# PMSM_500W_Controller_MCU.net
KiCad netlist of a schematic drawn in Altium Designer
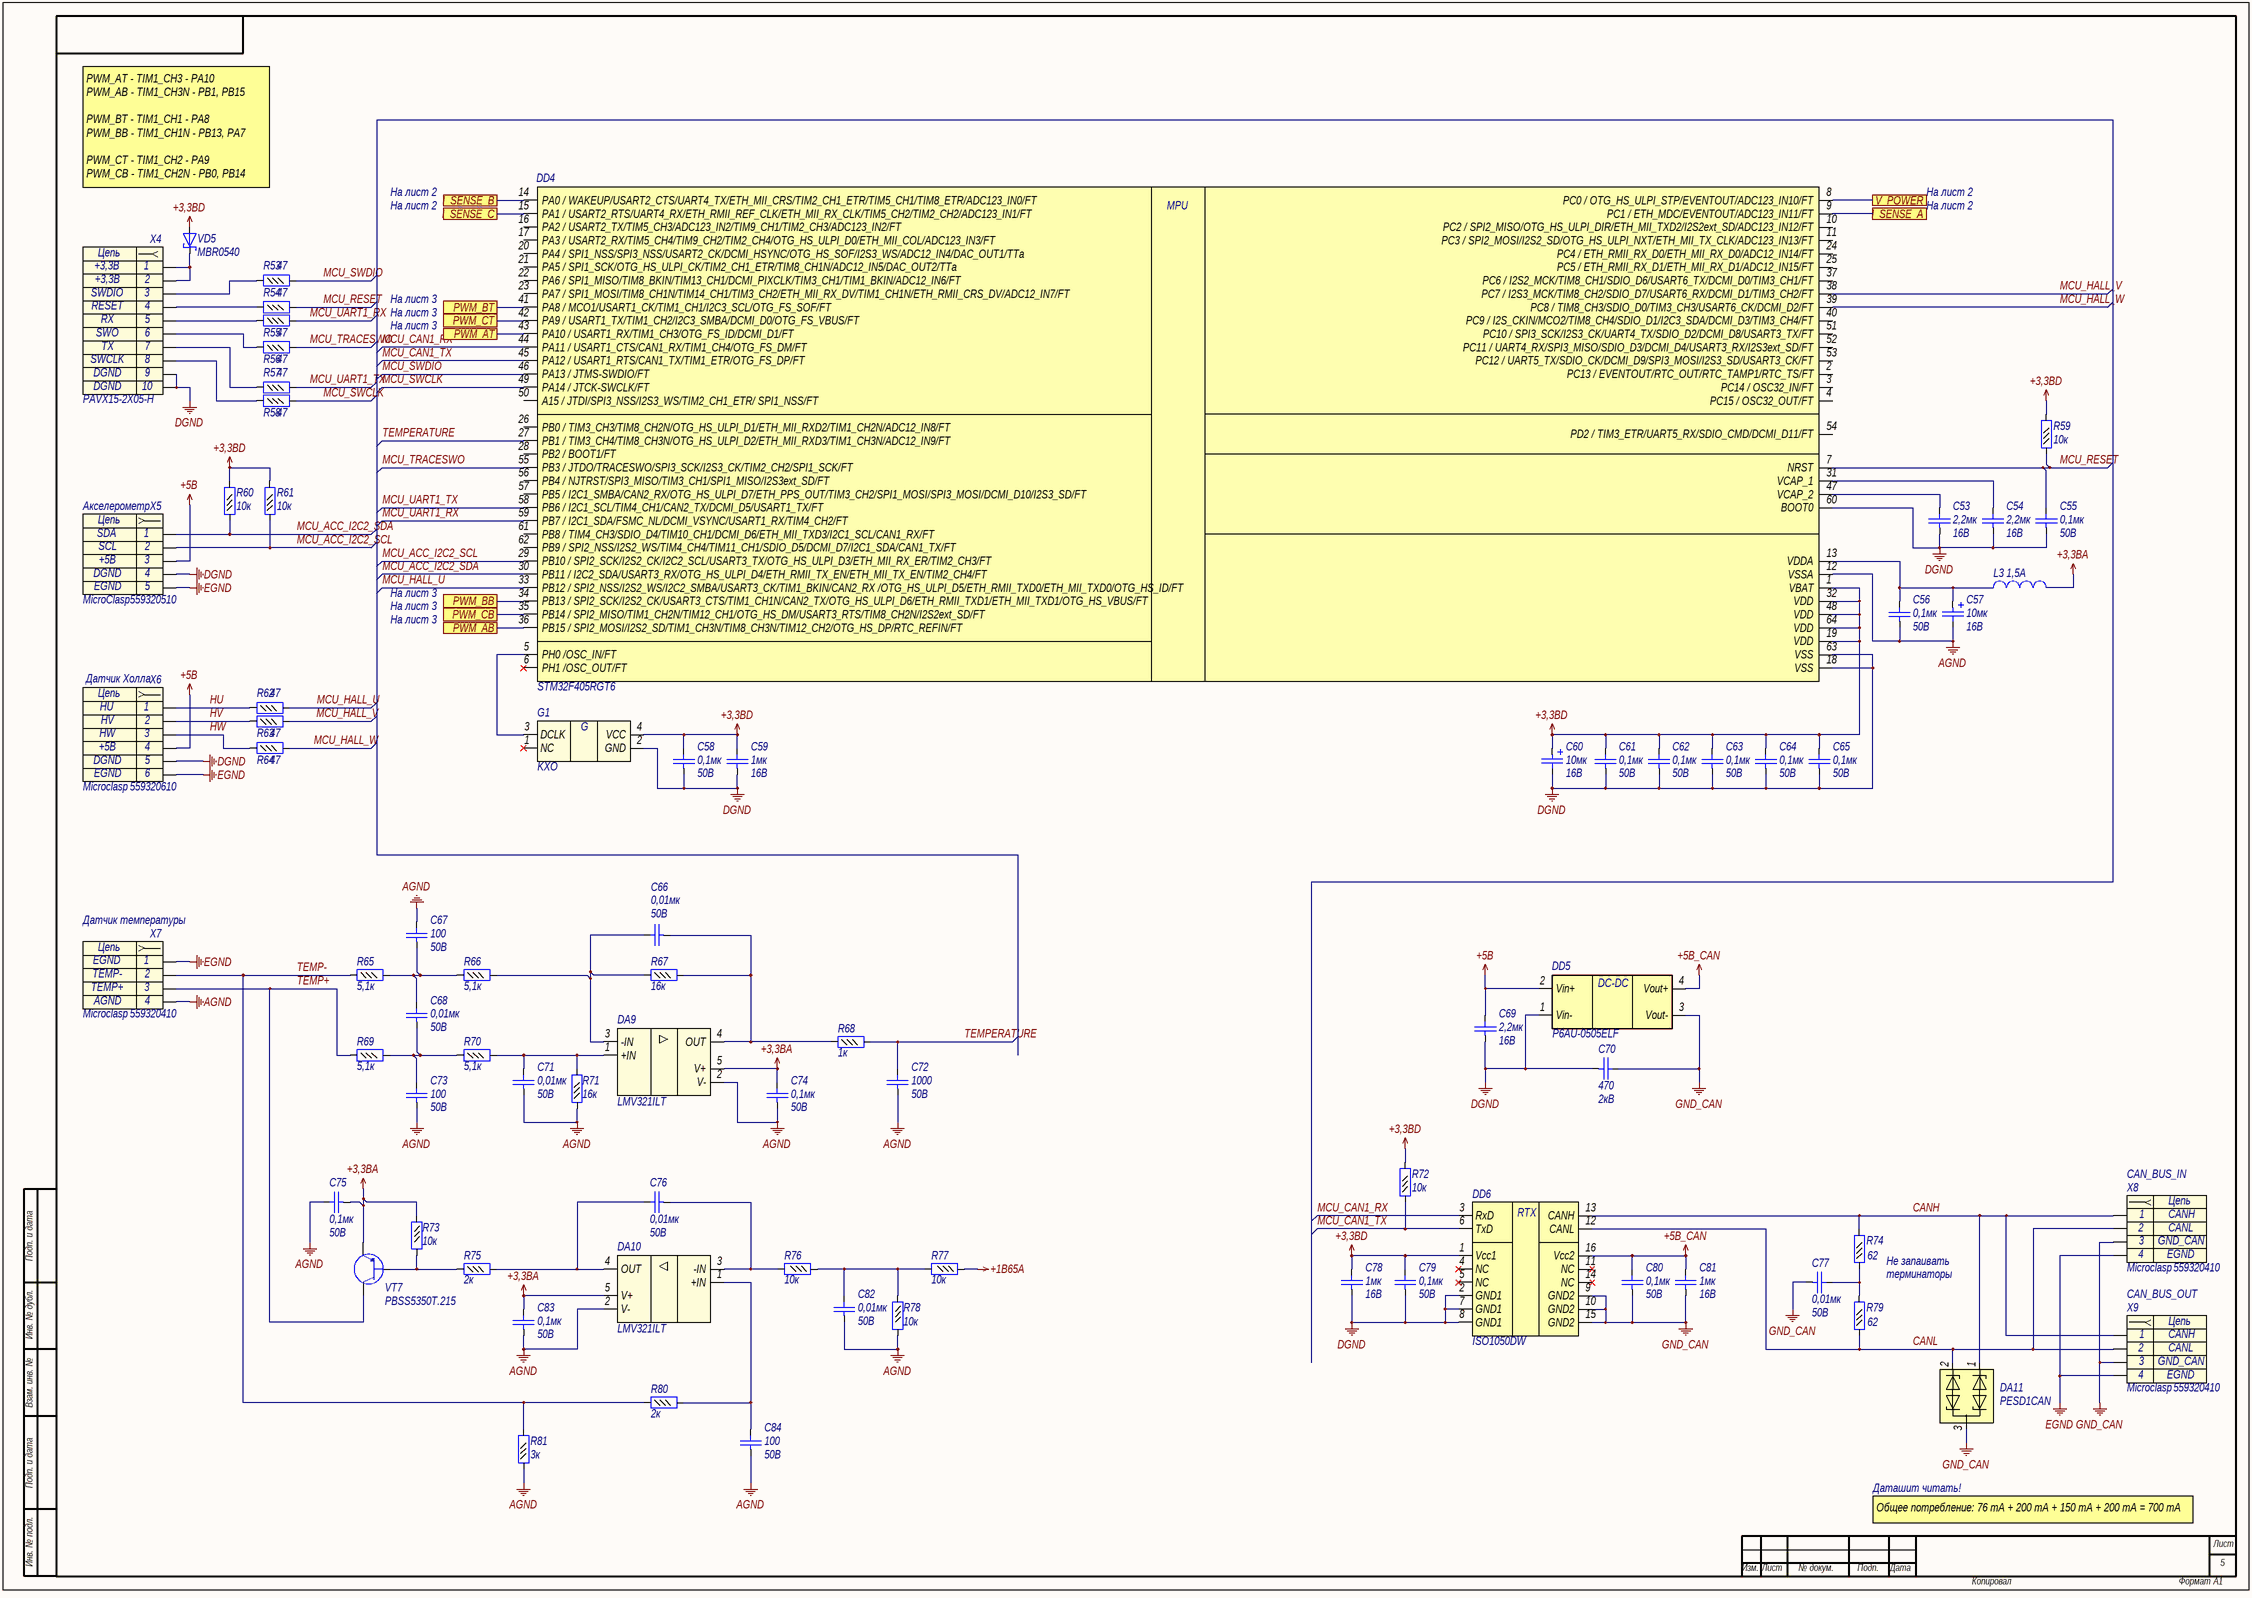
[diagram p0: PMSM_500W_Controller_MCU.SchDoc]

(export (version "E")
  (design (tool "Eeschema 10.0.6"))
  (components
    (comp (ref "C53")
      (value "2,2мк")
      (footprint "C0603")
      (description "Конденсатор")
      (fields (field (name "VOLTAGE") "16B") (field (name "PART NUMBER") "GRM188Z71C225ME43J"))
      (libsource (lib "MOP44") (part "Capacitor"))
    )
    (comp (ref "C54")
      (value "2,2мк")
      (footprint "C0603")
      (description "Конденсатор")
      (fields (field (name "VOLTAGE") "16B") (field (name "PART NUMBER") "GRM188Z71C225ME43J"))
      (libsource (lib "MOP44") (part "Capacitor"))
    )
    (comp (ref "C55")
      (value "0,1мк")
      (footprint "C0402")
      (description "Конденсатор")
      (fields
        (field (name "VOLTAGE") "50В")
        (field (name "PART NUMBER") "GRM155R71H104KE14D")
        (field (name "Comment") "Capacitor")
      )
      (libsource (lib "MOP44") (part "Capacitor"))
    )
    (comp (ref "C56")
      (value "0,1мк")
      (footprint "C0402")
      (description "Конденсатор")
      (fields
        (field (name "VOLTAGE") "50В")
        (field (name "PART NUMBER") "GRM155R71H104KE14D")
        (field (name "Comment") "Capacitor")
      )
      (libsource (lib "MOP44") (part "Capacitor"))
    )
    (comp (ref "C57")
      (value "10мк")
      (footprint "TANTAL CASE A")
      (description "Конденсатор полярный")
      (fields
        (field (name "VOLTAGE") "16В")
        (field (name "PART NUMBER") "293D106X9016A2TE3")
        (field (name "Comment") "Capacitor_pol")
      )
      (libsource (lib "MOP44") (part "Capacitor_pol"))
    )
    (comp (ref "C58")
      (value "0,1мк")
      (footprint "C0402")
      (description "Конденсатор")
      (fields
        (field (name "VOLTAGE") "50В")
        (field (name "PART NUMBER") "GRM155R71H104KE14D")
        (field (name "Comment") "Capacitor")
      )
      (libsource (lib "MOP44") (part "Capacitor"))
    )
    (comp (ref "C59")
      (value "1мк")
      (footprint "C0603")
      (description "Конденсатор")
      (fields
        (field (name "VOLTAGE") "16B")
        (field (name "PART NUMBER") "GRM188R71C105KA12D**")
        (field (name "Comment") "Capacitor")
      )
      (libsource (lib "MOP44") (part "Capacitor"))
    )
    (comp (ref "C60")
      (value "10мк")
      (footprint "TANTAL CASE A")
      (description "Конденсатор полярный")
      (fields
        (field (name "VOLTAGE") "16В")
        (field (name "PART NUMBER") "293D106X9016A2TE3")
        (field (name "Comment") "Capacitor_pol")
      )
      (libsource (lib "MOP44") (part "Capacitor_pol"))
    )
    (comp (ref "C61")
      (value "0,1мк")
      (footprint "C0402")
      (description "Конденсатор")
      (fields
        (field (name "VOLTAGE") "50В")
        (field (name "PART NUMBER") "GRM155R71H104KE14D")
        (field (name "Comment") "Capacitor")
      )
      (libsource (lib "MOP44") (part "Capacitor"))
    )
    (comp (ref "C62")
      (value "0,1мк")
      (footprint "C0402")
      (description "Конденсатор")
      (fields
        (field (name "VOLTAGE") "50В")
        (field (name "PART NUMBER") "GRM155R71H104KE14D")
        (field (name "Comment") "Capacitor")
      )
      (libsource (lib "MOP44") (part "Capacitor"))
    )
    (comp (ref "C63")
      (value "0,1мк")
      (footprint "C0402")
      (description "Конденсатор")
      (fields
        (field (name "VOLTAGE") "50В")
        (field (name "PART NUMBER") "GRM155R71H104KE14D")
        (field (name "Comment") "Capacitor")
      )
      (libsource (lib "MOP44") (part "Capacitor"))
    )
    (comp (ref "C64")
      (value "0,1мк")
      (footprint "C0402")
      (description "Конденсатор")
      (fields
        (field (name "VOLTAGE") "50В")
        (field (name "PART NUMBER") "GRM155R71H104KE14D")
        (field (name "Comment") "Capacitor")
      )
      (libsource (lib "MOP44") (part "Capacitor"))
    )
    (comp (ref "C65")
      (value "0,1мк")
      (footprint "C0402")
      (description "Конденсатор")
      (fields
        (field (name "VOLTAGE") "50В")
        (field (name "PART NUMBER") "GRM155R71H104KE14D")
        (field (name "Comment") "Capacitor")
      )
      (libsource (lib "MOP44") (part "Capacitor"))
    )
    (comp (ref "C66")
      (value "0,01мк")
      (footprint "C0402")
      (description "Конденсатор")
      (fields
        (field (name "VOLTAGE") "50B")
        (field (name "PART NUMBER") "GRM155R71H103K")
        (field (name "Comment") "Capacitor")
      )
      (libsource (lib "MOP44") (part "Capacitor"))
    )
    (comp (ref "C67")
      (value "100")
      (footprint "C0402")
      (description "Конденсатор")
      (fields
        (field (name "VOLTAGE") "50B")
        (field (name "PART NUMBER") "GRM1535C1H101J")
        (field (name "Comment") "Capacitor")
      )
      (libsource (lib "MOP44") (part "Capacitor"))
    )
    (comp (ref "C68")
      (value "0,01мк")
      (footprint "C0402")
      (description "Конденсатор")
      (fields
        (field (name "VOLTAGE") "50B")
        (field (name "PART NUMBER") "GRM155R71H103K")
        (field (name "Comment") "Capacitor")
      )
      (libsource (lib "MOP44") (part "Capacitor"))
    )
    (comp (ref "C69")
      (value "2,2мк")
      (footprint "C0603")
      (description "Конденсатор")
      (fields (field (name "VOLTAGE") "16B") (field (name "PART NUMBER") "GRM188Z71C225ME43J"))
      (libsource (lib "MOP44") (part "Capacitor"))
    )
    (comp (ref "C70")
      (value "470")
      (footprint "C1206")
      (description "Конденсатор")
      (fields
        (field (name "VOLTAGE") "2кВ")
        (field (name "PART NUMBER") "CC1206KKX7RDBB471")
        (field (name "Comment") "Capacitor")
      )
      (libsource (lib "MOP44") (part "Capacitor"))
    )
    (comp (ref "C71")
      (value "0,01мк")
      (footprint "C0402")
      (description "Конденсатор")
      (fields
        (field (name "VOLTAGE") "50B")
        (field (name "PART NUMBER") "GRM155R71H103K")
        (field (name "Comment") "Capacitor")
      )
      (libsource (lib "MOP44") (part "Capacitor"))
    )
    (comp (ref "C72")
      (value "1000")
      (footprint "C0402")
      (description "Конденсатор")
      (fields
        (field (name "VOLTAGE") "50B")
        (field (name "PART NUMBER") "GRM1555C1H102J")
        (field (name "Comment") "Capacitor")
      )
      (libsource (lib "MOP44") (part "Capacitor"))
    )
    (comp (ref "C73")
      (value "100")
      (footprint "C0402")
      (description "Конденсатор")
      (fields
        (field (name "VOLTAGE") "50B")
        (field (name "PART NUMBER") "GRM1535C1H101J")
        (field (name "Comment") "Capacitor")
      )
      (libsource (lib "MOP44") (part "Capacitor"))
    )
    (comp (ref "C74")
      (value "0,1мк")
      (footprint "C0402")
      (description "Конденсатор")
      (fields
        (field (name "VOLTAGE") "50В")
        (field (name "PART NUMBER") "GRM155R71H104KE14D")
        (field (name "Comment") "Capacitor")
      )
      (libsource (lib "MOP44") (part "Capacitor"))
    )
    (comp (ref "C75")
      (value "0,1мк")
      (footprint "C0402")
      (description "Конденсатор")
      (fields
        (field (name "VOLTAGE") "50В")
        (field (name "PART NUMBER") "GRM155R71H104KE14D")
        (field (name "Comment") "Capacitor")
      )
      (libsource (lib "MOP44") (part "Capacitor"))
    )
    (comp (ref "C76")
      (value "0,01мк")
      (footprint "C0402")
      (description "Конденсатор")
      (fields
        (field (name "VOLTAGE") "50B")
        (field (name "PART NUMBER") "GRM155R71H103K")
        (field (name "Comment") "Capacitor")
      )
      (libsource (lib "MOP44") (part "Capacitor"))
    )
    (comp (ref "C77")
      (value "0,01мк")
      (footprint "C0402")
      (description "Конденсатор")
      (fields
        (field (name "VOLTAGE") "50B")
        (field (name "PART NUMBER") "GRM155R71H103K")
        (field (name "Comment") "Capacitor")
      )
      (libsource (lib "MOP44") (part "Capacitor"))
    )
    (comp (ref "C78")
      (value "1мк")
      (footprint "C0603")
      (description "Конденсатор")
      (fields
        (field (name "VOLTAGE") "16B")
        (field (name "PART NUMBER") "GRM188R71C105KA12D**")
        (field (name "Comment") "Capacitor")
      )
      (libsource (lib "MOP44") (part "Capacitor"))
    )
    (comp (ref "C79")
      (value "0,1мк")
      (footprint "C0402")
      (description "Конденсатор")
      (fields
        (field (name "VOLTAGE") "50В")
        (field (name "PART NUMBER") "GRM155R71H104KE14D")
        (field (name "Comment") "Capacitor")
      )
      (libsource (lib "MOP44") (part "Capacitor"))
    )
    (comp (ref "C80")
      (value "0,1мк")
      (footprint "C0402")
      (description "Конденсатор")
      (fields
        (field (name "VOLTAGE") "50В")
        (field (name "PART NUMBER") "GRM155R71H104KE14D")
        (field (name "Comment") "Capacitor")
      )
      (libsource (lib "MOP44") (part "Capacitor"))
    )
    (comp (ref "C81")
      (value "1мк")
      (footprint "C0603")
      (description "Конденсатор")
      (fields
        (field (name "VOLTAGE") "16B")
        (field (name "PART NUMBER") "GRM188R71C105KA12D**")
        (field (name "Comment") "Capacitor")
      )
      (libsource (lib "MOP44") (part "Capacitor"))
    )
    (comp (ref "C82")
      (value "0,01мк")
      (footprint "C0402")
      (description "Конденсатор")
      (fields
        (field (name "VOLTAGE") "50B")
        (field (name "PART NUMBER") "GRM155R71H103K")
        (field (name "Comment") "Capacitor")
      )
      (libsource (lib "MOP44") (part "Capacitor"))
    )
    (comp (ref "C83")
      (value "0,1мк")
      (footprint "C0402")
      (description "Конденсатор")
      (fields
        (field (name "VOLTAGE") "50В")
        (field (name "PART NUMBER") "GRM155R71H104KE14D")
        (field (name "Comment") "Capacitor")
      )
      (libsource (lib "MOP44") (part "Capacitor"))
    )
    (comp (ref "C84")
      (value "100")
      (footprint "C0402")
      (description "Конденсатор")
      (fields
        (field (name "VOLTAGE") "50B")
        (field (name "PART NUMBER") "GRM1535C1H101J")
        (field (name "Comment") "Capacitor")
      )
      (libsource (lib "MOP44") (part "Capacitor"))
    )
    (comp (ref "DA9")
      (value "LMV321ILT")
      (footprint "SOT23-5")
      (description "HIGH-DRIVE OPERATIONAL AMPLIFIERS WITH SHUTDOWN")
      (libsource (lib "") (part "LMV321ILT_1"))
    )
    (comp (ref "DA10")
      (value "LMV321ILT")
      (footprint "SOT23-5")
      (description "HIGH-DRIVE OPERATIONAL AMPLIFIERS WITH SHUTDOWN")
      (libsource (lib "MOP44") (part "LMV321ILT"))
    )
    (comp (ref "DA11")
      (value "PESD")
      (footprint "SOT23-3")
      (description "TVS")
      (fields (field (name "PART NUMBER") "PESD1CAN"))
      (libsource (lib "MOP44") (part "PESD"))
    )
    (comp (ref "DD4")
      (value "STM32F405RGT6")
      (footprint "LQFP64")
      (libsource (lib "MOP44") (part "STM32F405RGT6"))
    )
    (comp (ref "DD5")
      (value "P6AU-xxxxELF")
      (footprint "SIP4")
      (description "DC/DC преобразователь")
      (fields (field (name "PART NUMBER") "P6AU-0505ELF") (field (name "MANUFACTURER") "PEAK Electronics"))
      (libsource (lib "MOP44") (part "P6AU-xxxxELF"))
    )
    (comp (ref "DD6")
      (value "~")
      (footprint "SO16")
      (description "Isolated CAN Transceiver")
      (fields (field (name "PART NUMBER") "ISO1050DW"))
      (libsource (lib "MOP44") (part "ISO1050DW"))
    )
    (comp (ref "G1")
      (value "KXO")
      (footprint "QSMD7x5.2x1.8")
      (description "Кварц. генер. 32.768 МГц (HCMOS/TTL)")
      (fields (field (name "PART NUMBER") "KXO-V97"))
      (libsource (lib "MOP44") (part "KXO"))
    )
    (comp (ref "L3")
      (value "Inductor")
      (footprint "L0603")
      (description "EMI Suppression Filter")
      (fields (field (name "RATED CURRENT") "1,5A") (field (name "PART NUMBER") "BLM18PG181SN1D"))
      (libsource (lib "MOP44") (part "Inductor"))
    )
    (comp (ref "R53")
      (value "47")
      (footprint "R0402")
      (description "Резистор")
      (fields (field (name "PART NUMBER") "RC0402FR-0747RL") (field (name "POWER") "0,062Вт"))
      (libsource (lib "MOP44") (part "Resistor_0,062Вт"))
    )
    (comp (ref "R54")
      (value "47")
      (footprint "R0402")
      (description "Резистор")
      (fields (field (name "PART NUMBER") "RC0402FR-0747RL") (field (name "POWER") "0,062Вт"))
      (libsource (lib "MOP44") (part "Resistor_0,062Вт"))
    )
    (comp (ref "R55")
      (value "47")
      (footprint "R0402")
      (description "Резистор")
      (fields (field (name "PART NUMBER") "RC0402FR-0747RL") (field (name "POWER") "0,062Вт"))
      (libsource (lib "MOP44") (part "Resistor_0,062Вт"))
    )
    (comp (ref "R56")
      (value "47")
      (footprint "R0402")
      (description "Резистор")
      (fields (field (name "PART NUMBER") "RC0402FR-0747RL") (field (name "POWER") "0,062Вт"))
      (libsource (lib "MOP44") (part "Resistor_0,062Вт"))
    )
    (comp (ref "R57")
      (value "47")
      (footprint "R0402")
      (description "Резистор")
      (fields (field (name "PART NUMBER") "RC0402FR-0747RL") (field (name "POWER") "0,062Вт"))
      (libsource (lib "MOP44") (part "Resistor_0,062Вт"))
    )
    (comp (ref "R58")
      (value "47")
      (footprint "R0402")
      (description "Резистор")
      (fields (field (name "PART NUMBER") "RC0402FR-0747RL") (field (name "POWER") "0,062Вт"))
      (libsource (lib "MOP44") (part "Resistor_0,062Вт"))
    )
    (comp (ref "R59")
      (value "10к")
      (footprint "R0402")
      (description "Резистор")
      (fields (field (name "PART NUMBER") "RC0402FR-0710KL") (field (name "POWER") "0,062Вт"))
      (libsource (lib "") (part "Resistor_0,062Вт_2"))
    )
    (comp (ref "R60")
      (value "10к")
      (footprint "R0402")
      (description "Резистор")
      (fields (field (name "PART NUMBER") "RC0402FR-0710KL") (field (name "POWER") "0,062Вт"))
      (libsource (lib "") (part "Resistor_0,062Вт_2"))
    )
    (comp (ref "R61")
      (value "10к")
      (footprint "R0402")
      (description "Резистор")
      (fields (field (name "PART NUMBER") "RC0402FR-0710KL") (field (name "POWER") "0,062Вт"))
      (libsource (lib "") (part "Resistor_0,062Вт_2"))
    )
    (comp (ref "R62")
      (value "47")
      (footprint "R0402")
      (description "Резистор")
      (fields (field (name "PART NUMBER") "RC0402FR-0747RL") (field (name "POWER") "0,062Вт"))
      (libsource (lib "MOP44") (part "Resistor_0,062Вт"))
    )
    (comp (ref "R63")
      (value "47")
      (footprint "R0402")
      (description "Резистор")
      (fields (field (name "PART NUMBER") "RC0402FR-0747RL") (field (name "POWER") "0,062Вт"))
      (libsource (lib "MOP44") (part "Resistor_0,062Вт"))
    )
    (comp (ref "R64")
      (value "47")
      (footprint "R0402")
      (description "Резистор")
      (fields (field (name "PART NUMBER") "RC0402FR-0747RL") (field (name "POWER") "0,062Вт"))
      (libsource (lib "MOP44") (part "Resistor_0,062Вт"))
    )
    (comp (ref "R65")
      (value "5,1к")
      (footprint "R0402")
      (description "Резистор")
      (fields (field (name "PART NUMBER") "RC0402FR-075K1") (field (name "POWER") "0,062Вт"))
      (libsource (lib "MOP44") (part "Resistor_0,062Вт"))
    )
    (comp (ref "R66")
      (value "5,1к")
      (footprint "R0402")
      (description "Резистор")
      (fields (field (name "PART NUMBER") "RC0402FR-075K1") (field (name "POWER") "0,062Вт"))
      (libsource (lib "MOP44") (part "Resistor_0,062Вт"))
    )
    (comp (ref "R67")
      (value "16к")
      (footprint "R0402")
      (description "Резистор")
      (fields (field (name "PART NUMBER") "RC0402FR-0716KL") (field (name "POWER") "0,062Вт"))
      (libsource (lib "MOP44") (part "Resistor_0,062Вт"))
    )
    (comp (ref "R68")
      (value "1к")
      (footprint "R0402")
      (description "Резистор")
      (fields (field (name "PART NUMBER") "RC0402FR-071KL") (field (name "POWER") "0,062Вт"))
      (libsource (lib "MOP44") (part "Resistor_0,062Вт"))
    )
    (comp (ref "R69")
      (value "5,1к")
      (footprint "R0402")
      (description "Резистор")
      (fields (field (name "PART NUMBER") "RC0402FR-075K1") (field (name "POWER") "0,062Вт"))
      (libsource (lib "MOP44") (part "Resistor_0,062Вт"))
    )
    (comp (ref "R70")
      (value "5,1к")
      (footprint "R0402")
      (description "Резистор")
      (fields (field (name "PART NUMBER") "RC0402FR-075K1") (field (name "POWER") "0,062Вт"))
      (libsource (lib "MOP44") (part "Resistor_0,062Вт"))
    )
    (comp (ref "R71")
      (value "16к")
      (footprint "R0402")
      (description "Резистор")
      (fields (field (name "PART NUMBER") "RC0402FR-0716KL") (field (name "POWER") "0,062Вт"))
      (libsource (lib "") (part "Resistor_0,062Вт_2"))
    )
    (comp (ref "R72")
      (value "10к")
      (footprint "R0402")
      (description "Резистор")
      (fields (field (name "PART NUMBER") "RC0402FR-0710KL") (field (name "POWER") "0,062Вт"))
      (libsource (lib "") (part "Resistor_0,062Вт_2"))
    )
    (comp (ref "R73")
      (value "10к")
      (footprint "R0402")
      (description "Резистор")
      (fields (field (name "PART NUMBER") "RC0402FR-0710KL") (field (name "POWER") "0,062Вт"))
      (libsource (lib "") (part "Resistor_0,062Вт_1"))
    )
    (comp (ref "R74")
      (value "62")
      (footprint "R0402")
      (description "Резистор")
      (fields (field (name "PART NUMBER") "RC0402FR-0762RL") (field (name "POWER") "0,062Вт"))
      (libsource (lib "") (part "Resistor_0,062Вт_2"))
    )
    (comp (ref "R75")
      (value "2к")
      (footprint "R0402")
      (description "Резистор")
      (fields (field (name "PART NUMBER") "RC0402FR-072KL") (field (name "POWER") "0,062Вт"))
      (libsource (lib "MOP44") (part "Resistor_0,062Вт"))
    )
    (comp (ref "R76")
      (value "10к")
      (footprint "R0402")
      (description "Резистор")
      (fields (field (name "PART NUMBER") "RC0402FR-0710KL") (field (name "POWER") "0,062Вт"))
      (libsource (lib "") (part "Resistor_0,062Вт_3"))
    )
    (comp (ref "R77")
      (value "10к")
      (footprint "R0402")
      (description "Резистор")
      (fields (field (name "PART NUMBER") "RC0402FR-0710KL") (field (name "POWER") "0,062Вт"))
      (libsource (lib "") (part "Resistor_0,062Вт_3"))
    )
    (comp (ref "R78")
      (value "10к")
      (footprint "R0402")
      (description "Резистор")
      (fields (field (name "PART NUMBER") "RC0402FR-0710KL") (field (name "POWER") "0,062Вт"))
      (libsource (lib "") (part "Resistor_0,062Вт_1"))
    )
    (comp (ref "R79")
      (value "62")
      (footprint "R0402")
      (description "Резистор")
      (fields (field (name "PART NUMBER") "RC0402FR-0762RL") (field (name "POWER") "0,062Вт"))
      (libsource (lib "") (part "Resistor_0,062Вт_2"))
    )
    (comp (ref "R80")
      (value "2к")
      (footprint "R0402")
      (description "Резистор")
      (fields (field (name "PART NUMBER") "RC0402FR-072KL") (field (name "POWER") "0,062Вт"))
      (libsource (lib "MOP44") (part "Resistor_0,062Вт"))
    )
    (comp (ref "R81")
      (value "3к")
      (footprint "R0402")
      (description "Резистор")
      (fields (field (name "PART NUMBER") "RC0402FR-073KL") (field (name "POWER") "0,062Вт"))
      (libsource (lib "") (part "Resistor_0,062Вт_2"))
    )
    (comp (ref "VD5")
      (value "DiodeSchottky")
      (footprint "SOD-123")
      (description "Диод Шоттки")
      (fields (field (name "PART NUMBER") "MBR0540"))
      (libsource (lib "MOP44") (part "DiodeSchottky"))
    )
    (comp (ref "VT7")
      (value "BJT PNP")
      (footprint "SOT23-3")
      (fields (field (name "POWER") "0,48Вт") (field (name "PART NUMBER") "PBSS5350T.215"))
      (libsource (lib "MOP44") (part "BJT PNP"))
    )
    (comp (ref "X4")
      (value "Header_10_sct")
      (footprint "PAVX15-2X05-H")
      (description "Разъем - 10 конт. розетка")
      (fields (field (name "PART NUMBER") "PAVX15-2X05-H"))
      (libsource (lib "MOP44") (part "Header_10_sct"))
    )
    (comp (ref "X5")
      (value "Акселерометр")
      (footprint "MOLEX_559320510")
      (description "Разъем - 5 конт. розетка")
      (fields (field (name "PART NAME") "MicroClasp") (field (name "PART NUMBER") "559320510"))
      (libsource (lib "MOP44") (part "Header_5_sct"))
    )
    (comp (ref "X6")
      (value "Датчик Холла")
      (footprint "MOLEX_559320610")
      (description "Разъем - 6 конт. розетка")
      (fields (field (name "PART NUMBER") "559320610"))
      (libsource (lib "MOP44") (part "Header_6_sct"))
    )
    (comp (ref "X7")
      (value "Датчик температуры")
      (footprint "MOLEX_559320410")
      (description "Разъем - 4 конт. розетка")
      (fields (field (name "PART NUMBER") "559320410"))
      (libsource (lib "") (part "Header_4_sct_1"))
    )
    (comp (ref "X8")
      (value "CAN_BUS_IN")
      (footprint "MOLEX_559320410")
      (description "Разъем - 4 конт. розетка")
      (fields (field (name "PART NUMBER") "559320410"))
      (libsource (lib "MOP44") (part "Header_4_sct"))
    )
    (comp (ref "X9")
      (value "CAN_BUS_OUT")
      (footprint "MOLEX_559320410")
      (description "Разъем - 4 конт. розетка")
      (fields (field (name "PART NUMBER") "559320410"))
      (libsource (lib "MOP44") (part "Header_4_sct"))
    )
  )
  (nets
    (net (code "1") (name "+1B65A") (class "Default")
      (node (ref "R77") (pin "1") (pinfunction "1_1") (pintype "passive"))
    )
    (net (code "2") (name "+3,3BA") (class "Default")
      (node (ref "C74") (pin "2") (pinfunction "2_2") (pintype "passive"))
      (node (ref "C75") (pin "1") (pinfunction "1_1") (pintype "passive"))
      (node (ref "C83") (pin "2") (pinfunction "2_2") (pintype "passive"))
      (node (ref "DA10") (pin "5") (pinfunction "V+_5") (pintype "passive"))
      (node (ref "DA9") (pin "5") (pinfunction "V+_5") (pintype "passive"))
      (node (ref "L3") (pin "2") (pinfunction "2_2") (pintype "passive"))
      (node (ref "R73") (pin "1") (pinfunction "1_1") (pintype "passive"))
      (node (ref "VT7") (pin "2") (pinfunction "E_2") (pintype "passive"))
    )
    (net (code "3") (name "+3,3BD") (class "Default")
      (node (ref "C58") (pin "2") (pinfunction "2_2") (pintype "passive"))
      (node (ref "C59") (pin "2") (pinfunction "2_2") (pintype "passive"))
      (node (ref "C60") (pin "1") (pinfunction "1_1") (pintype "passive"))
      (node (ref "C61") (pin "2") (pinfunction "2_2") (pintype "passive"))
      (node (ref "C62") (pin "2") (pinfunction "2_2") (pintype "passive"))
      (node (ref "C63") (pin "2") (pinfunction "2_2") (pintype "passive"))
      (node (ref "C64") (pin "2") (pinfunction "2_2") (pintype "passive"))
      (node (ref "C65") (pin "2") (pinfunction "2_2") (pintype "passive"))
      (node (ref "C78") (pin "2") (pinfunction "2_2") (pintype "passive"))
      (node (ref "C79") (pin "2") (pinfunction "2_2") (pintype "passive"))
      (node (ref "DD4") (pin "1") (pinfunction "VBAT_1") (pintype "passive"))
      (node (ref "DD4") (pin "19") (pinfunction "VDD_19") (pintype "passive"))
      (node (ref "DD4") (pin "32") (pinfunction "VDD_32") (pintype "passive"))
      (node (ref "DD4") (pin "48") (pinfunction "VDD_48") (pintype "passive"))
      (node (ref "DD4") (pin "64") (pinfunction "VDD_64") (pintype "passive"))
      (node (ref "DD6") (pin "1") (pinfunction "Vcc1_1") (pintype "passive"))
      (node (ref "G1") (pin "4") (pinfunction "VCC_4") (pintype "power_in"))
      (node (ref "R59") (pin "2") (pinfunction "2_2") (pintype "passive"))
      (node (ref "R60") (pin "2") (pinfunction "2_2") (pintype "passive"))
      (node (ref "R61") (pin "2") (pinfunction "2_2") (pintype "passive"))
      (node (ref "R72") (pin "2") (pinfunction "2_2") (pintype "passive"))
      (node (ref "VD5") (pin "2") (pinfunction "A_2") (pintype "passive"))
    )
    (net (code "4") (name "+5B") (class "Default")
      (node (ref "C69") (pin "2") (pinfunction "2_2") (pintype "passive"))
      (node (ref "DD5") (pin "2") (pinfunction "Vin+_2") (pintype "passive"))
      (node (ref "X5") (pin "3") (pinfunction "3_3") (pintype "passive"))
      (node (ref "X6") (pin "4") (pinfunction "4_4") (pintype "passive"))
    )
    (net (code "5") (name "+5B_CAN") (class "Default")
      (node (ref "C80") (pin "2") (pinfunction "2_2") (pintype "passive"))
      (node (ref "C81") (pin "2") (pinfunction "2_2") (pintype "passive"))
      (node (ref "DD5") (pin "4") (pinfunction "Vout+_4") (pintype "passive"))
      (node (ref "DD6") (pin "16") (pinfunction "Vcc2_16") (pintype "passive"))
    )
    (net (code "6") (name "/CANH") (class "Default")
      (node (ref "DA11") (pin "1") (pintype "passive"))
      (node (ref "DD6") (pin "13") (pinfunction "CANH_13") (pintype "passive"))
      (node (ref "R74") (pin "2") (pinfunction "2_2") (pintype "passive"))
      (node (ref "X8") (pin "1") (pinfunction "1_1") (pintype "passive"))
      (node (ref "X9") (pin "1") (pinfunction "1_1") (pintype "passive"))
    )
    (net (code "7") (name "/CANL") (class "Default")
      (node (ref "DA11") (pin "2") (pinfunction "1_2") (pintype "passive"))
      (node (ref "DD6") (pin "12") (pinfunction "CANL_12") (pintype "passive"))
      (node (ref "R79") (pin "1") (pinfunction "1_1") (pintype "passive"))
      (node (ref "X8") (pin "2") (pinfunction "2_2") (pintype "passive"))
      (node (ref "X9") (pin "2") (pinfunction "2_2") (pintype "passive"))
    )
    (net (code "8") (name "/HU") (class "Default")
      (node (ref "R62") (pin "1") (pinfunction "1_1") (pintype "passive"))
      (node (ref "X6") (pin "1") (pinfunction "1_1") (pintype "passive"))
    )
    (net (code "9") (name "/HV") (class "Default")
      (node (ref "R63") (pin "1") (pinfunction "1_1") (pintype "passive"))
      (node (ref "X6") (pin "2") (pinfunction "2_2") (pintype "passive"))
    )
    (net (code "10") (name "/HW") (class "Default")
      (node (ref "R64") (pin "1") (pinfunction "1_1") (pintype "passive"))
      (node (ref "X6") (pin "3") (pinfunction "3_3") (pintype "passive"))
    )
    (net (code "11") (name "/I_SENSE_A") (class "Default")
      (node (ref "DD4") (pin "9") (pinfunction "PC1_/_ETH_MDC/EVENTOUT/ADC123_IN11/FT_9") (pintype "passive"))
    )
    (net (code "12") (name "/I_SENSE_B") (class "Default")
      (node (ref "DD4") (pin "14") (pinfunction "PA0_/_WAKEUP/USART2_CTS/UART4_TX/ETH_MII_CRS/TIM2_CH1_ETR/TIM5_CH1/TIM8_ETR/ADC123_IN0/FT_14") (pintype "passive"))
    )
    (net (code "13") (name "/I_SENSE_C") (class "Default")
      (node (ref "DD4") (pin "15") (pinfunction "PA1_/_USART2_RTS/UART4_RX/ETH_RMII_REF_CLK/ETH_MII_RX_CLK/TIM5_CH2/TIM2_CH2/ADC123_IN1/FT_15") (pintype "passive"))
    )
    (net (code "14") (name "/MCU_ACC_I2C2_SCL") (class "Default")
      (node (ref "DD4") (pin "29") (pinfunction "PB10_/_SPI2_SCK/I2S2_CK/I2C2_SCL/USART3_TX/OTG_HS_ULPI_D3/ETH_MII_RX_ER/TIM2_CH3/FT_29") (pintype "passive"))
      (node (ref "R61") (pin "1") (pinfunction "1_1") (pintype "passive"))
      (node (ref "X5") (pin "2") (pinfunction "2_2") (pintype "passive"))
    )
    (net (code "15") (name "/MCU_ACC_I2C2_SDA") (class "Default")
      (node (ref "DD4") (pin "30") (pinfunction "PB11_/_I2C2_SDA/USART3_RX/OTG_HS_ULPI_D4/ETH_RMII_TX_EN/ETH_MII_TX_EN/TIM2_CH4/FT_30") (pintype "passive"))
      (node (ref "R60") (pin "1") (pinfunction "1_1") (pintype "passive"))
      (node (ref "X5") (pin "1") (pinfunction "1_1") (pintype "passive"))
    )
    (net (code "16") (name "/MCU_CAN1_RX") (class "Default")
      (node (ref "DD4") (pin "44") (pinfunction "PA11_/_USART1_CTS/CAN1_RX/TIM1_CH4/OTG_FS_DM/FT_44") (pintype "passive"))
      (node (ref "DD6") (pin "3") (pinfunction "RxD_3") (pintype "passive"))
    )
    (net (code "17") (name "/MCU_CAN1_TX") (class "Default")
      (node (ref "DD4") (pin "45") (pinfunction "PA12_/_USART1_RTS/CAN1_TX/TIM1_ETR/OTG_FS_DP/FT_45") (pintype "passive"))
      (node (ref "DD6") (pin "6") (pinfunction "TxD_6") (pintype "passive"))
      (node (ref "R72") (pin "1") (pinfunction "1_1") (pintype "passive"))
    )
    (net (code "18") (name "/MCU_HALL_U") (class "Default")
      (node (ref "DD4") (pin "33") (pinfunction "PB12_/_SPI2_NSS/I2S2_WS/I2C2_SMBA/USART3_CK/TIM1_BKIN/CAN2_RX_/OTG_HS_ULPI_D5/ETH_RMII_TXD0/ETH_MII_TXD0/OTG_HS_ID/FT_33") (pintype "passive"))
      (node (ref "R62") (pin "2") (pinfunction "2_2") (pintype "passive"))
    )
    (net (code "19") (name "/MCU_HALL_V") (class "Default")
      (node (ref "DD4") (pin "38") (pinfunction "PC7_/_I2S3_MCK/TIM8_CH2/SDIO_D7/USART6_RX/DCMI_D1/TIM3_CH2/FT_38") (pintype "passive"))
      (node (ref "R63") (pin "2") (pinfunction "2_2") (pintype "passive"))
    )
    (net (code "20") (name "/MCU_HALL_W") (class "Default")
      (node (ref "DD4") (pin "39") (pinfunction "PC8_/_TIM8_CH3/SDIO_D0/TIM3_CH3/USART6_CK/DCMI_D2/FT_39") (pintype "passive"))
      (node (ref "R64") (pin "2") (pinfunction "2_2") (pintype "passive"))
    )
    (net (code "21") (name "/MCU_RESET") (class "Default")
      (node (ref "C55") (pin "2") (pinfunction "2_2") (pintype "passive"))
      (node (ref "DD4") (pin "7") (pinfunction "NRST_7") (pintype "passive"))
      (node (ref "R54") (pin "2") (pinfunction "2_2") (pintype "passive"))
      (node (ref "R59") (pin "1") (pinfunction "1_1") (pintype "passive"))
    )
    (net (code "22") (name "/MCU_SWCLK") (class "Default")
      (node (ref "DD4") (pin "49") (pinfunction "PA14_/_JTCK-SWCLK/FT_49") (pintype "passive"))
      (node (ref "R58") (pin "2") (pinfunction "2_2") (pintype "passive"))
    )
    (net (code "23") (name "/MCU_SWDIO") (class "Default")
      (node (ref "DD4") (pin "46") (pinfunction "PA13_/_JTMS-SWDIO/FT_46") (pintype "passive"))
      (node (ref "R53") (pin "2") (pinfunction "2_2") (pintype "passive"))
    )
    (net (code "24") (name "/MCU_TRACESWO") (class "Default")
      (node (ref "DD4") (pin "55") (pinfunction "PB3_/_JTDO/TRACESWO/SPI3_SCK/I2S3_CK/TIM2_CH2/SPI1_SCK/FT_55") (pintype "passive"))
      (node (ref "R56") (pin "2") (pinfunction "2_2") (pintype "passive"))
    )
    (net (code "25") (name "/MCU_UART1_RX") (class "Default")
      (node (ref "DD4") (pin "59") (pinfunction "PB7_/_I2C1_SDA/FSMC_NL/DCMI_VSYNC/USART1_RX/TIM4_CH2/FT_59") (pintype "passive"))
      (node (ref "R55") (pin "2") (pinfunction "2_2") (pintype "passive"))
    )
    (net (code "26") (name "/MCU_UART1_TX") (class "Default")
      (node (ref "DD4") (pin "58") (pinfunction "PB6_/_I2C1_SCL/TIM4_CH1/CAN2_TX/DCMI_D5/USART1_TX/FT_58") (pintype "passive"))
      (node (ref "R57") (pin "2") (pinfunction "2_2") (pintype "passive"))
    )
    (net (code "27") (name "/PWM_AB") (class "Default")
      (node (ref "DD4") (pin "36") (pinfunction "PB15_/_SPI2_MOSI/I2S2_SD/TIM1_CH3N/TIM8_CH3N/TIM12_CH2/OTG_HS_DP/RTC_REFIN/FT_36") (pintype "passive"))
    )
    (net (code "28") (name "/PWM_AT") (class "Default")
      (node (ref "DD4") (pin "43") (pinfunction "PA10_/_USART1_RX/TIM1_CH3/OTG_FS_ID/DCMI_D1/FT_43") (pintype "passive"))
    )
    (net (code "29") (name "/PWM_BB") (class "Default")
      (node (ref "DD4") (pin "34") (pinfunction "PB13_/_SPI2_SCK/I2S2_CK/USART3_CTS/TIM1_CH1N/CAN2_TX/OTG_HS_ULPI_D6/ETH_RMII_TXD1/ETH_MII_TXD1/OTG_HS_VBUS/FT_34") (pintype "passive"))
    )
    (net (code "30") (name "/PWM_BT") (class "Default")
      (node (ref "DD4") (pin "41") (pinfunction "PA8_/_MCO1/USART1_CK/TIM1_CH1/I2C3_SCL/OTG_FS_SOF/FT_41") (pintype "passive"))
    )
    (net (code "31") (name "/PWM_CB") (class "Default")
      (node (ref "DD4") (pin "35") (pinfunction "PB14_/_SPI2_MISO/TIM1_CH2N/TIM12_CH1/OTG_HS_DM/USART3_RTS/TIM8_CH2N/I2S2ext_SD/FT_35") (pintype "passive"))
    )
    (net (code "32") (name "/PWM_CT") (class "Default")
      (node (ref "DD4") (pin "42") (pinfunction "PA9_/_USART1_TX/TIM1_CH2/I2C3_SMBA/DCMI_D0/OTG_FS_VBUS/FT_42") (pintype "passive"))
    )
    (net (code "33") (name "/TEMP+") (class "Default")
      (node (ref "R69") (pin "1") (pinfunction "1_1") (pintype "passive"))
      (node (ref "VT7") (pin "3") (pinfunction "C_3") (pintype "passive"))
      (node (ref "X7") (pin "3") (pinfunction "3_3") (pintype "passive"))
    )
    (net (code "34") (name "/TEMP-") (class "Default")
      (node (ref "R65") (pin "1") (pinfunction "1_1") (pintype "passive"))
      (node (ref "R80") (pin "1") (pinfunction "1_1") (pintype "passive"))
      (node (ref "R81") (pin "2") (pinfunction "2_2") (pintype "passive"))
      (node (ref "X7") (pin "2") (pinfunction "2_2") (pintype "passive"))
    )
    (net (code "35") (name "/TEMPERATURE") (class "Default")
      (node (ref "C72") (pin "2") (pinfunction "2_2") (pintype "passive"))
      (node (ref "DD4") (pin "27") (pinfunction "PB1_/_TIM3_CH4/TIM8_CH3N/OTG_HS_ULPI_D2/ETH_MII_RXD3/TIM1_CH3N/ADC12_IN9/FT_27") (pintype "passive"))
      (node (ref "R68") (pin "2") (pinfunction "2_2") (pintype "passive"))
    )
    (net (code "36") (name "/V_POWER") (class "Default")
      (node (ref "DD4") (pin "8") (pinfunction "PC0_/_OTG_HS_ULPI_STP/EVENTOUT/ADC123_IN10/FT_8") (pintype "passive"))
    )
    (net (code "37") (name "AGND") (class "Default")
      (node (ref "C56") (pin "1") (pinfunction "1_1") (pintype "passive"))
      (node (ref "C57") (pin "2") (pinfunction "2_2") (pintype "passive"))
      (node (ref "C67") (pin "2") (pinfunction "2_2") (pintype "passive"))
      (node (ref "C71") (pin "1") (pinfunction "1_1") (pintype "passive"))
      (node (ref "C72") (pin "1") (pinfunction "1_1") (pintype "passive"))
      (node (ref "C73") (pin "1") (pinfunction "1_1") (pintype "passive"))
      (node (ref "C74") (pin "1") (pinfunction "1_1") (pintype "passive"))
      (node (ref "C75") (pin "2") (pinfunction "2_2") (pintype "passive"))
      (node (ref "C82") (pin "1") (pinfunction "1_1") (pintype "passive"))
      (node (ref "C83") (pin "1") (pinfunction "1_1") (pintype "passive"))
      (node (ref "C84") (pin "1") (pinfunction "1_1") (pintype "passive"))
      (node (ref "DA10") (pin "2") (pinfunction "V-_2") (pintype "passive"))
      (node (ref "DA9") (pin "2") (pinfunction "V-_2") (pintype "passive"))
      (node (ref "DD4") (pin "12") (pinfunction "VSSA_12") (pintype "passive"))
      (node (ref "R71") (pin "1") (pinfunction "1_1") (pintype "passive"))
      (node (ref "R78") (pin "2") (pinfunction "2_2") (pintype "passive"))
      (node (ref "R81") (pin "1") (pinfunction "1_1") (pintype "passive"))
      (node (ref "X7") (pin "4") (pinfunction "4_4") (pintype "passive"))
    )
    (net (code "38") (name "DGND") (class "Default")
      (node (ref "C53") (pin "1") (pinfunction "1_1") (pintype "passive"))
      (node (ref "C54") (pin "1") (pinfunction "1_1") (pintype "passive"))
      (node (ref "C55") (pin "1") (pinfunction "1_1") (pintype "passive"))
      (node (ref "C58") (pin "1") (pinfunction "1_1") (pintype "passive"))
      (node (ref "C59") (pin "1") (pinfunction "1_1") (pintype "passive"))
      (node (ref "C60") (pin "2") (pinfunction "2_2") (pintype "passive"))
      (node (ref "C61") (pin "1") (pinfunction "1_1") (pintype "passive"))
      (node (ref "C62") (pin "1") (pinfunction "1_1") (pintype "passive"))
      (node (ref "C63") (pin "1") (pinfunction "1_1") (pintype "passive"))
      (node (ref "C64") (pin "1") (pinfunction "1_1") (pintype "passive"))
      (node (ref "C65") (pin "1") (pinfunction "1_1") (pintype "passive"))
      (node (ref "C69") (pin "1") (pinfunction "1_1") (pintype "passive"))
      (node (ref "C70") (pin "1") (pinfunction "1_1") (pintype "passive"))
      (node (ref "C78") (pin "1") (pinfunction "1_1") (pintype "passive"))
      (node (ref "C79") (pin "1") (pinfunction "1_1") (pintype "passive"))
      (node (ref "DD4") (pin "18") (pinfunction "VSS_18") (pintype "passive"))
      (node (ref "DD4") (pin "60") (pinfunction "BOOT0_60") (pintype "passive"))
      (node (ref "DD4") (pin "63") (pinfunction "VSS_63") (pintype "passive"))
      (node (ref "DD5") (pin "1") (pinfunction "Vin-_1") (pintype "passive"))
      (node (ref "DD6") (pin "2") (pinfunction "GND1_2") (pintype "passive"))
      (node (ref "DD6") (pin "7") (pinfunction "GND1_7") (pintype "passive"))
      (node (ref "DD6") (pin "8") (pinfunction "GND1_8") (pintype "passive"))
      (node (ref "G1") (pin "2") (pinfunction "GND_2") (pintype "power_in"))
      (node (ref "X4") (pin "10") (pinfunction "10_10") (pintype "passive"))
      (node (ref "X4") (pin "9") (pinfunction "9_9") (pintype "passive"))
      (node (ref "X5") (pin "4") (pinfunction "4_4") (pintype "passive"))
      (node (ref "X6") (pin "5") (pinfunction "5_5") (pintype "passive"))
    )
    (net (code "39") (name "EGND") (class "Default")
      (node (ref "X5") (pin "5") (pinfunction "5_5") (pintype "passive"))
      (node (ref "X6") (pin "6") (pinfunction "6_6") (pintype "passive"))
      (node (ref "X7") (pin "1") (pinfunction "1_1") (pintype "passive"))
      (node (ref "X8") (pin "4") (pinfunction "4_4") (pintype "passive"))
      (node (ref "X9") (pin "4") (pinfunction "4_4") (pintype "passive"))
    )
    (net (code "40") (name "GND_CAN") (class "Default")
      (node (ref "C70") (pin "2") (pinfunction "2_2") (pintype "passive"))
      (node (ref "C77") (pin "1") (pinfunction "1_1") (pintype "passive"))
      (node (ref "C80") (pin "1") (pinfunction "1_1") (pintype "passive"))
      (node (ref "C81") (pin "1") (pinfunction "1_1") (pintype "passive"))
      (node (ref "DA11") (pin "3") (pintype "passive"))
      (node (ref "DD5") (pin "3") (pinfunction "Vout-_3") (pintype "passive"))
      (node (ref "DD6") (pin "10") (pinfunction "GND2_10") (pintype "passive"))
      (node (ref "DD6") (pin "15") (pinfunction "GND2_15") (pintype "passive"))
      (node (ref "DD6") (pin "9") (pinfunction "GND2_9") (pintype "passive"))
      (node (ref "X8") (pin "3") (pinfunction "3_3") (pintype "passive"))
      (node (ref "X9") (pin "3") (pinfunction "3_3") (pintype "passive"))
    )
    (net (code "41") (name "Net-(C67-Pad1)") (class "Default")
      (node (ref "C67") (pin "1") (pinfunction "1_1") (pintype "passive"))
      (node (ref "C68") (pin "2") (pinfunction "2_2") (pintype "passive"))
      (node (ref "R65") (pin "2") (pinfunction "2_2") (pintype "passive"))
      (node (ref "R66") (pin "1") (pinfunction "1_1") (pintype "passive"))
    )
    (net (code "42") (name "Net-(C68-Pad1)") (class "Default")
      (node (ref "C68") (pin "1") (pinfunction "1_1") (pintype "passive"))
      (node (ref "C73") (pin "2") (pinfunction "2_2") (pintype "passive"))
      (node (ref "R69") (pin "2") (pinfunction "2_2") (pintype "passive"))
      (node (ref "R70") (pin "1") (pinfunction "1_1") (pintype "passive"))
    )
    (net (code "43") (name "Net-(C77-Pad2)") (class "Default")
      (node (ref "C77") (pin "2") (pinfunction "2_2") (pintype "passive"))
      (node (ref "R74") (pin "1") (pinfunction "1_1") (pintype "passive"))
      (node (ref "R79") (pin "2") (pinfunction "2_2") (pintype "passive"))
    )
    (net (code "44") (name "Net-(C82-Pad2)") (class "Default")
      (node (ref "C82") (pin "2") (pinfunction "2_2") (pintype "passive"))
      (node (ref "R76") (pin "1") (pinfunction "1_1") (pintype "passive"))
      (node (ref "R77") (pin "2") (pinfunction "2_2") (pintype "passive"))
      (node (ref "R78") (pin "1") (pinfunction "1_1") (pintype "passive"))
    )
    (net (code "45") (name "Net-(DA9-+IN)") (class "Default")
      (node (ref "C71") (pin "2") (pinfunction "2_2") (pintype "passive"))
      (node (ref "DA9") (pin "1") (pinfunction "+IN_1") (pintype "passive"))
      (node (ref "R70") (pin "2") (pinfunction "2_2") (pintype "passive"))
      (node (ref "R71") (pin "2") (pinfunction "2_2") (pintype "passive"))
    )
    (net (code "46") (name "Net-(DA9--IN)") (class "Default")
      (node (ref "C66") (pin "2") (pinfunction "2_2") (pintype "passive"))
      (node (ref "DA9") (pin "3") (pinfunction "-IN_3") (pintype "passive"))
      (node (ref "R66") (pin "2") (pinfunction "2_2") (pintype "passive"))
      (node (ref "R67") (pin "1") (pinfunction "1_1") (pintype "passive"))
    )
    (net (code "47") (name "Net-(DA9-OUT)") (class "Default")
      (node (ref "C66") (pin "1") (pinfunction "1_1") (pintype "passive"))
      (node (ref "DA9") (pin "4") (pinfunction "OUT_4") (pintype "passive"))
      (node (ref "R67") (pin "2") (pinfunction "2_2") (pintype "passive"))
      (node (ref "R68") (pin "1") (pinfunction "1_1") (pintype "passive"))
    )
    (net (code "48") (name "Net-(DA10-+IN)") (class "Default")
      (node (ref "C84") (pin "2") (pinfunction "2_2") (pintype "passive"))
      (node (ref "DA10") (pin "1") (pinfunction "+IN_1") (pintype "passive"))
      (node (ref "R80") (pin "2") (pinfunction "2_2") (pintype "passive"))
    )
    (net (code "49") (name "Net-(DA10--IN)") (class "Default")
      (node (ref "C76") (pin "1") (pinfunction "1_1") (pintype "passive"))
      (node (ref "DA10") (pin "3") (pinfunction "-IN_3") (pintype "passive"))
      (node (ref "R76") (pin "2") (pinfunction "2_2") (pintype "passive"))
    )
    (net (code "50") (name "Net-(DA10-OUT)") (class "Default")
      (node (ref "C76") (pin "2") (pinfunction "2_2") (pintype "passive"))
      (node (ref "DA10") (pin "4") (pinfunction "OUT_4") (pintype "passive"))
      (node (ref "R75") (pin "2") (pinfunction "2_2") (pintype "passive"))
    )
    (net (code "51") (name "Net-(DD4-PH0_{slash}OSC_IN{slash}FT)") (class "Default")
      (node (ref "DD4") (pin "5") (pinfunction "PH0_/OSC_IN/FT_5") (pintype "passive"))
      (node (ref "G1") (pin "3") (pinfunction "DCLK_3") (pintype "power_in"))
    )
    (net (code "52") (name "Net-(DD4-VCAP_1)") (class "Default")
      (node (ref "C54") (pin "2") (pinfunction "2_2") (pintype "passive"))
      (node (ref "DD4") (pin "31") (pinfunction "VCAP_1_31") (pintype "passive"))
    )
    (net (code "53") (name "Net-(DD4-VCAP_2)") (class "Default")
      (node (ref "C53") (pin "2") (pinfunction "2_2") (pintype "passive"))
      (node (ref "DD4") (pin "47") (pinfunction "VCAP_2_47") (pintype "passive"))
    )
    (net (code "54") (name "Net-(DD4-VDDA)") (class "Default")
      (node (ref "C56") (pin "2") (pinfunction "2_2") (pintype "passive"))
      (node (ref "C57") (pin "1") (pinfunction "1_1") (pintype "passive"))
      (node (ref "DD4") (pin "13") (pinfunction "VDDA_13") (pintype "passive"))
      (node (ref "L3") (pin "1") (pinfunction "1_1") (pintype "passive"))
    )
    (net (code "55") (name "Net-(R53-Pad1)") (class "Default")
      (node (ref "R53") (pin "1") (pinfunction "1_1") (pintype "passive"))
      (node (ref "X4") (pin "3") (pinfunction "3_3") (pintype "passive"))
    )
    (net (code "56") (name "Net-(R54-Pad1)") (class "Default")
      (node (ref "R54") (pin "1") (pinfunction "1_1") (pintype "passive"))
      (node (ref "X4") (pin "4") (pinfunction "4_4") (pintype "passive"))
    )
    (net (code "57") (name "Net-(R55-Pad1)") (class "Default")
      (node (ref "R55") (pin "1") (pinfunction "1_1") (pintype "passive"))
      (node (ref "X4") (pin "5") (pinfunction "5_5") (pintype "passive"))
    )
    (net (code "58") (name "Net-(R56-Pad1)") (class "Default")
      (node (ref "R56") (pin "1") (pinfunction "1_1") (pintype "passive"))
      (node (ref "X4") (pin "6") (pinfunction "6_6") (pintype "passive"))
    )
    (net (code "59") (name "Net-(R57-Pad1)") (class "Default")
      (node (ref "R57") (pin "1") (pinfunction "1_1") (pintype "passive"))
      (node (ref "X4") (pin "7") (pinfunction "7_7") (pintype "passive"))
    )
    (net (code "60") (name "Net-(R58-Pad1)") (class "Default")
      (node (ref "R58") (pin "1") (pinfunction "1_1") (pintype "passive"))
      (node (ref "X4") (pin "8") (pinfunction "8_8") (pintype "passive"))
    )
    (net (code "61") (name "Net-(VD5-K)") (class "Default")
      (node (ref "VD5") (pin "1") (pinfunction "K_1") (pintype "passive"))
      (node (ref "X4") (pin "1") (pinfunction "1_1") (pintype "passive"))
      (node (ref "X4") (pin "2") (pinfunction "2_2") (pintype "passive"))
    )
    (net (code "62") (name "Net-(VT7-B)") (class "Default")
      (node (ref "R73") (pin "2") (pinfunction "2_2") (pintype "passive"))
      (node (ref "R75") (pin "1") (pinfunction "1_1") (pintype "passive"))
      (node (ref "VT7") (pin "1") (pinfunction "B_1") (pintype "passive"))
    )
    (net (code "63") (name "unconnected-(DD4-A15_{slash}_JTDI{slash}SPI3_NSS{slash}I2S3_WS{slash}TIM2_CH1_ETR{slash}_SPI1_NSS{slash}FT-Pad50)") (class "Default")
      (node (ref "DD4") (pin "50") (pinfunction "A15_/_JTDI/SPI3_NSS/I2S3_WS/TIM2_CH1_ETR/_SPI1_NSS/FT_50") (pintype "passive"))
    )
    (net (code "64") (name "unconnected-(DD4-PA2_{slash}_USART2_TX{slash}TIM5_CH3{slash}ADC123_IN2{slash}TIM9_CH1{slash}TIM2_CH3{slash}ADC123_IN2{slash}FT-Pad16)") (class "Default")
      (node (ref "DD4") (pin "16") (pinfunction "PA2_/_USART2_TX/TIM5_CH3/ADC123_IN2/TIM9_CH1/TIM2_CH3/ADC123_IN2/FT_16") (pintype "passive"))
    )
    (net (code "65") (name "unconnected-(DD4-PA3_{slash}_USART2_RX{slash}TIM5_CH4{slash}TIM9_CH2{slash}TIM2_CH4{slash}OTG_HS_ULPI_D0{slash}ETH_MII_COL{slash}ADC123_IN3{slash}FT-Pad17)") (class "Default")
      (node (ref "DD4") (pin "17") (pinfunction "PA3_/_USART2_RX/TIM5_CH4/TIM9_CH2/TIM2_CH4/OTG_HS_ULPI_D0/ETH_MII_COL/ADC123_IN3/FT_17") (pintype "passive"))
    )
    (net (code "66") (name "unconnected-(DD4-PA4_{slash}_SPI1_NSS{slash}SPI3_NSS{slash}USART2_CK{slash}DCMI_HSYNC{slash}OTG_HS_SOF{slash}I2S3_WS{slash}ADC12_IN4{slash}DAC_OUT1{slash}TTa-Pad20)") (class "Default")
      (node (ref "DD4") (pin "20") (pinfunction "PA4_/_SPI1_NSS/SPI3_NSS/USART2_CK/DCMI_HSYNC/OTG_HS_SOF/I2S3_WS/ADC12_IN4/DAC_OUT1/TTa_20") (pintype "passive"))
    )
    (net (code "67") (name "unconnected-(DD4-PA5_{slash}_SPI1_SCK{slash}OTG_HS_ULPI_CK{slash}TIM2_CH1_ETR{slash}TIM8_CH1N{slash}ADC12_IN5{slash}DAC_OUT2{slash}TTa-Pad21)") (class "Default")
      (node (ref "DD4") (pin "21") (pinfunction "PA5_/_SPI1_SCK/OTG_HS_ULPI_CK/TIM2_CH1_ETR/TIM8_CH1N/ADC12_IN5/DAC_OUT2/TTa_21") (pintype "passive"))
    )
    (net (code "68") (name "unconnected-(DD4-PA6_{slash}_SPI1_MISO{slash}TIM8_BKIN{slash}TIM13_CH1{slash}DCMI_PIXCLK{slash}TIM3_CH1{slash}TIM1_BKIN{slash}ADC12_IN6{slash}FT-Pad22)") (class "Default")
      (node (ref "DD4") (pin "22") (pinfunction "PA6_/_SPI1_MISO/TIM8_BKIN/TIM13_CH1/DCMI_PIXCLK/TIM3_CH1/TIM1_BKIN/ADC12_IN6/FT_22") (pintype "passive"))
    )
    (net (code "69") (name "unconnected-(DD4-PA7_{slash}_SPI1_MOSI{slash}TIM8_CH1N{slash}TIM14_CH1{slash}TIM3_CH2{slash}ETH_MII_RX_DV{slash}TIM1_CH1N{slash}ETH_RMII_CRS_DV{slash}ADC12_IN7{slash}FT-Pad23)") (class "Default")
      (node (ref "DD4") (pin "23") (pinfunction "PA7_/_SPI1_MOSI/TIM8_CH1N/TIM14_CH1/TIM3_CH2/ETH_MII_RX_DV/TIM1_CH1N/ETH_RMII_CRS_DV/ADC12_IN7/FT_23") (pintype "passive"))
    )
    (net (code "70") (name "unconnected-(DD4-PB0_{slash}_TIM3_CH3{slash}TIM8_CH2N{slash}OTG_HS_ULPI_D1{slash}ETH_MII_RXD2{slash}TIM1_CH2N{slash}ADC12_IN8{slash}FT-Pad26)") (class "Default")
      (node (ref "DD4") (pin "26") (pinfunction "PB0_/_TIM3_CH3/TIM8_CH2N/OTG_HS_ULPI_D1/ETH_MII_RXD2/TIM1_CH2N/ADC12_IN8/FT_26") (pintype "passive"))
    )
    (net (code "71") (name "unconnected-(DD4-PB2_{slash}_BOOT1{slash}FT-Pad28)") (class "Default")
      (node (ref "DD4") (pin "28") (pinfunction "PB2_/_BOOT1/FT_28") (pintype "passive"))
    )
    (net (code "72") (name "unconnected-(DD4-PB4_{slash}_NJTRST{slash}SPI3_MISO{slash}TIM3_CH1{slash}SPI1_MISO{slash}I2S3ext_SD{slash}FT-Pad56)") (class "Default")
      (node (ref "DD4") (pin "56") (pinfunction "PB4_/_NJTRST/SPI3_MISO/TIM3_CH1/SPI1_MISO/I2S3ext_SD/FT_56") (pintype "passive"))
    )
    (net (code "73") (name "unconnected-(DD4-PB5_{slash}_I2C1_SMBA{slash}CAN2_RX{slash}OTG_HS_ULPI_D7{slash}ETH_PPS_OUT{slash}TIM3_CH2{slash}SPI1_MOSI{slash}SPI3_MOSI{slash}DCMI_D10{slash}I2S3_SD{slash}FT-Pad57)") (class "Default")
      (node (ref "DD4") (pin "57") (pinfunction "PB5_/_I2C1_SMBA/CAN2_RX/OTG_HS_ULPI_D7/ETH_PPS_OUT/TIM3_CH2/SPI1_MOSI/SPI3_MOSI/DCMI_D10/I2S3_SD/FT_57") (pintype "passive"))
    )
    (net (code "74") (name "unconnected-(DD4-PB8_{slash}_TIM4_CH3{slash}SDIO_D4{slash}TIM10_CH1{slash}DCMI_D6{slash}ETH_MII_TXD3{slash}I2C1_SCL{slash}CAN1_RX{slash}FT-Pad61)") (class "Default")
      (node (ref "DD4") (pin "61") (pinfunction "PB8_/_TIM4_CH3/SDIO_D4/TIM10_CH1/DCMI_D6/ETH_MII_TXD3/I2C1_SCL/CAN1_RX/FT_61") (pintype "passive"))
    )
    (net (code "75") (name "unconnected-(DD4-PB9_{slash}_SPI2_NSS{slash}I2S2_WS{slash}TIM4_CH4{slash}TIM11_CH1{slash}SDIO_D5{slash}DCMI_D7{slash}I2C1_SDA{slash}CAN1_TX{slash}FT-Pad62)") (class "Default")
      (node (ref "DD4") (pin "62") (pinfunction "PB9_/_SPI2_NSS/I2S2_WS/TIM4_CH4/TIM11_CH1/SDIO_D5/DCMI_D7/I2C1_SDA/CAN1_TX/FT_62") (pintype "passive"))
    )
    (net (code "76") (name "unconnected-(DD4-PC2_{slash}_SPI2_MISO{slash}OTG_HS_ULPI_DIR{slash}ETH_MII_TXD2{slash}I2S2ext_SD{slash}ADC123_IN12{slash}FT-Pad10)") (class "Default")
      (node (ref "DD4") (pin "10") (pinfunction "PC2_/_SPI2_MISO/OTG_HS_ULPI_DIR/ETH_MII_TXD2/I2S2ext_SD/ADC123_IN12/FT_10") (pintype "passive"))
    )
    (net (code "77") (name "unconnected-(DD4-PC3_{slash}_SPI2_MOSI{slash}I2S2_SD{slash}OTG_HS_ULPI_NXT{slash}ETH_MII_TX_CLK{slash}ADC123_IN13{slash}FT-Pad11)") (class "Default")
      (node (ref "DD4") (pin "11") (pinfunction "PC3_/_SPI2_MOSI/I2S2_SD/OTG_HS_ULPI_NXT/ETH_MII_TX_CLK/ADC123_IN13/FT_11") (pintype "passive"))
    )
    (net (code "78") (name "unconnected-(DD4-PC4_{slash}_ETH_RMII_RX_D0{slash}ETH_MII_RX_D0{slash}ADC12_IN14{slash}FT-Pad24)") (class "Default")
      (node (ref "DD4") (pin "24") (pinfunction "PC4_/_ETH_RMII_RX_D0/ETH_MII_RX_D0/ADC12_IN14/FT_24") (pintype "passive"))
    )
    (net (code "79") (name "unconnected-(DD4-PC5_{slash}_ETH_RMII_RX_D1{slash}ETH_MII_RX_D1{slash}ADC12_IN15{slash}FT-Pad25)") (class "Default")
      (node (ref "DD4") (pin "25") (pinfunction "PC5_/_ETH_RMII_RX_D1/ETH_MII_RX_D1/ADC12_IN15/FT_25") (pintype "passive"))
    )
    (net (code "80") (name "unconnected-(DD4-PC6_{slash}_I2S2_MCK{slash}TIM8_CH1{slash}SDIO_D6{slash}USART6_TX{slash}DCMI_D0{slash}TIM3_CH1{slash}FT-Pad37)") (class "Default")
      (node (ref "DD4") (pin "37") (pinfunction "PC6_/_I2S2_MCK/TIM8_CH1/SDIO_D6/USART6_TX/DCMI_D0/TIM3_CH1/FT_37") (pintype "passive"))
    )
    (net (code "81") (name "unconnected-(DD4-PC9_{slash}_I2S_CKIN{slash}MCO2{slash}TIM8_CH4{slash}SDIO_D1{slash}I2C3_SDA{slash}DCMI_D3{slash}TIM3_CH4{slash}FT-Pad40)") (class "Default")
      (node (ref "DD4") (pin "40") (pinfunction "PC9_/_I2S_CKIN/MCO2/TIM8_CH4/SDIO_D1/I2C3_SDA/DCMI_D3/TIM3_CH4/FT_40") (pintype "passive"))
    )
    (net (code "82") (name "unconnected-(DD4-PC10_{slash}_SPI3_SCK{slash}I2S3_CK{slash}UART4_TX{slash}SDIO_D2{slash}DCMI_D8{slash}USART3_TX{slash}FT-Pad51)") (class "Default")
      (node (ref "DD4") (pin "51") (pinfunction "PC10_/_SPI3_SCK/I2S3_CK/UART4_TX/SDIO_D2/DCMI_D8/USART3_TX/FT_51") (pintype "passive"))
    )
    (net (code "83") (name "unconnected-(DD4-PC11_{slash}_UART4_RX{slash}SPI3_MISO{slash}SDIO_D3{slash}DCMI_D4{slash}USART3_RX{slash}I2S3ext_SD{slash}FT-Pad52)") (class "Default")
      (node (ref "DD4") (pin "52") (pinfunction "PC11_/_UART4_RX/SPI3_MISO/SDIO_D3/DCMI_D4/USART3_RX/I2S3ext_SD/FT_52") (pintype "passive"))
    )
    (net (code "84") (name "unconnected-(DD4-PC12_{slash}_UART5_TX{slash}SDIO_CK{slash}DCMI_D9{slash}SPI3_MOSI{slash}I2S3_SD{slash}USART3_CK{slash}FT-Pad53)") (class "Default")
      (node (ref "DD4") (pin "53") (pinfunction "PC12_/_UART5_TX/SDIO_CK/DCMI_D9/SPI3_MOSI/I2S3_SD/USART3_CK/FT_53") (pintype "passive"))
    )
    (net (code "85") (name "unconnected-(DD4-PC13_{slash}_EVENTOUT{slash}RTC_OUT{slash}RTC_TAMP1{slash}RTC_TS{slash}FT-Pad2)") (class "Default")
      (node (ref "DD4") (pin "2") (pinfunction "PC13_/_EVENTOUT/RTC_OUT/RTC_TAMP1/RTC_TS/FT_2") (pintype "passive"))
    )
    (net (code "86") (name "unconnected-(DD4-PC14_{slash}_OSC32_IN{slash}FT-Pad3)") (class "Default")
      (node (ref "DD4") (pin "3") (pinfunction "PC14_/_OSC32_IN/FT_3") (pintype "passive"))
    )
    (net (code "87") (name "unconnected-(DD4-PC15_{slash}_OSC32_OUT{slash}FT-Pad4)") (class "Default")
      (node (ref "DD4") (pin "4") (pinfunction "PC15_/_OSC32_OUT/FT_4") (pintype "passive"))
    )
    (net (code "88") (name "unconnected-(DD4-PD2_{slash}_TIM3_ETR{slash}UART5_RX{slash}SDIO_CMD{slash}DCMI_D11{slash}FT-Pad54)") (class "Default")
      (node (ref "DD4") (pin "54") (pinfunction "PD2_/_TIM3_ETR/UART5_RX/SDIO_CMD/DCMI_D11/FT_54") (pintype "passive"))
    )
    (net (code "89") (name "unconnected-(DD4-PH1_{slash}OSC_OUT{slash}FT-Pad6)") (class "Default")
      (node (ref "DD4") (pin "6") (pinfunction "PH1_/OSC_OUT/FT_6") (pintype "passive+no_connect"))
    )
    (net (code "90") (name "unconnected-(DD6-NC-Pad4)") (class "Default")
      (node (ref "DD6") (pin "4") (pinfunction "NC_4") (pintype "passive+no_connect"))
    )
    (net (code "91") (name "unconnected-(DD6-NC-Pad5)") (class "Default")
      (node (ref "DD6") (pin "5") (pinfunction "NC_5") (pintype "passive+no_connect"))
    )
    (net (code "92") (name "unconnected-(DD6-NC-Pad11)") (class "Default")
      (node (ref "DD6") (pin "11") (pinfunction "NC_11") (pintype "passive+no_connect"))
    )
    (net (code "93") (name "unconnected-(DD6-NC-Pad14)") (class "Default")
      (node (ref "DD6") (pin "14") (pinfunction "NC_14") (pintype "passive+no_connect"))
    )
    (net (code "94") (name "unconnected-(G1-NC-Pad1)") (class "Default")
      (node (ref "G1") (pin "1") (pinfunction "NC_1") (pintype "power_in+no_connect"))
    )
  )
)
